# 200W_4FET_Load_v10.net
KiCad netlist of a schematic drawn in EAGLE
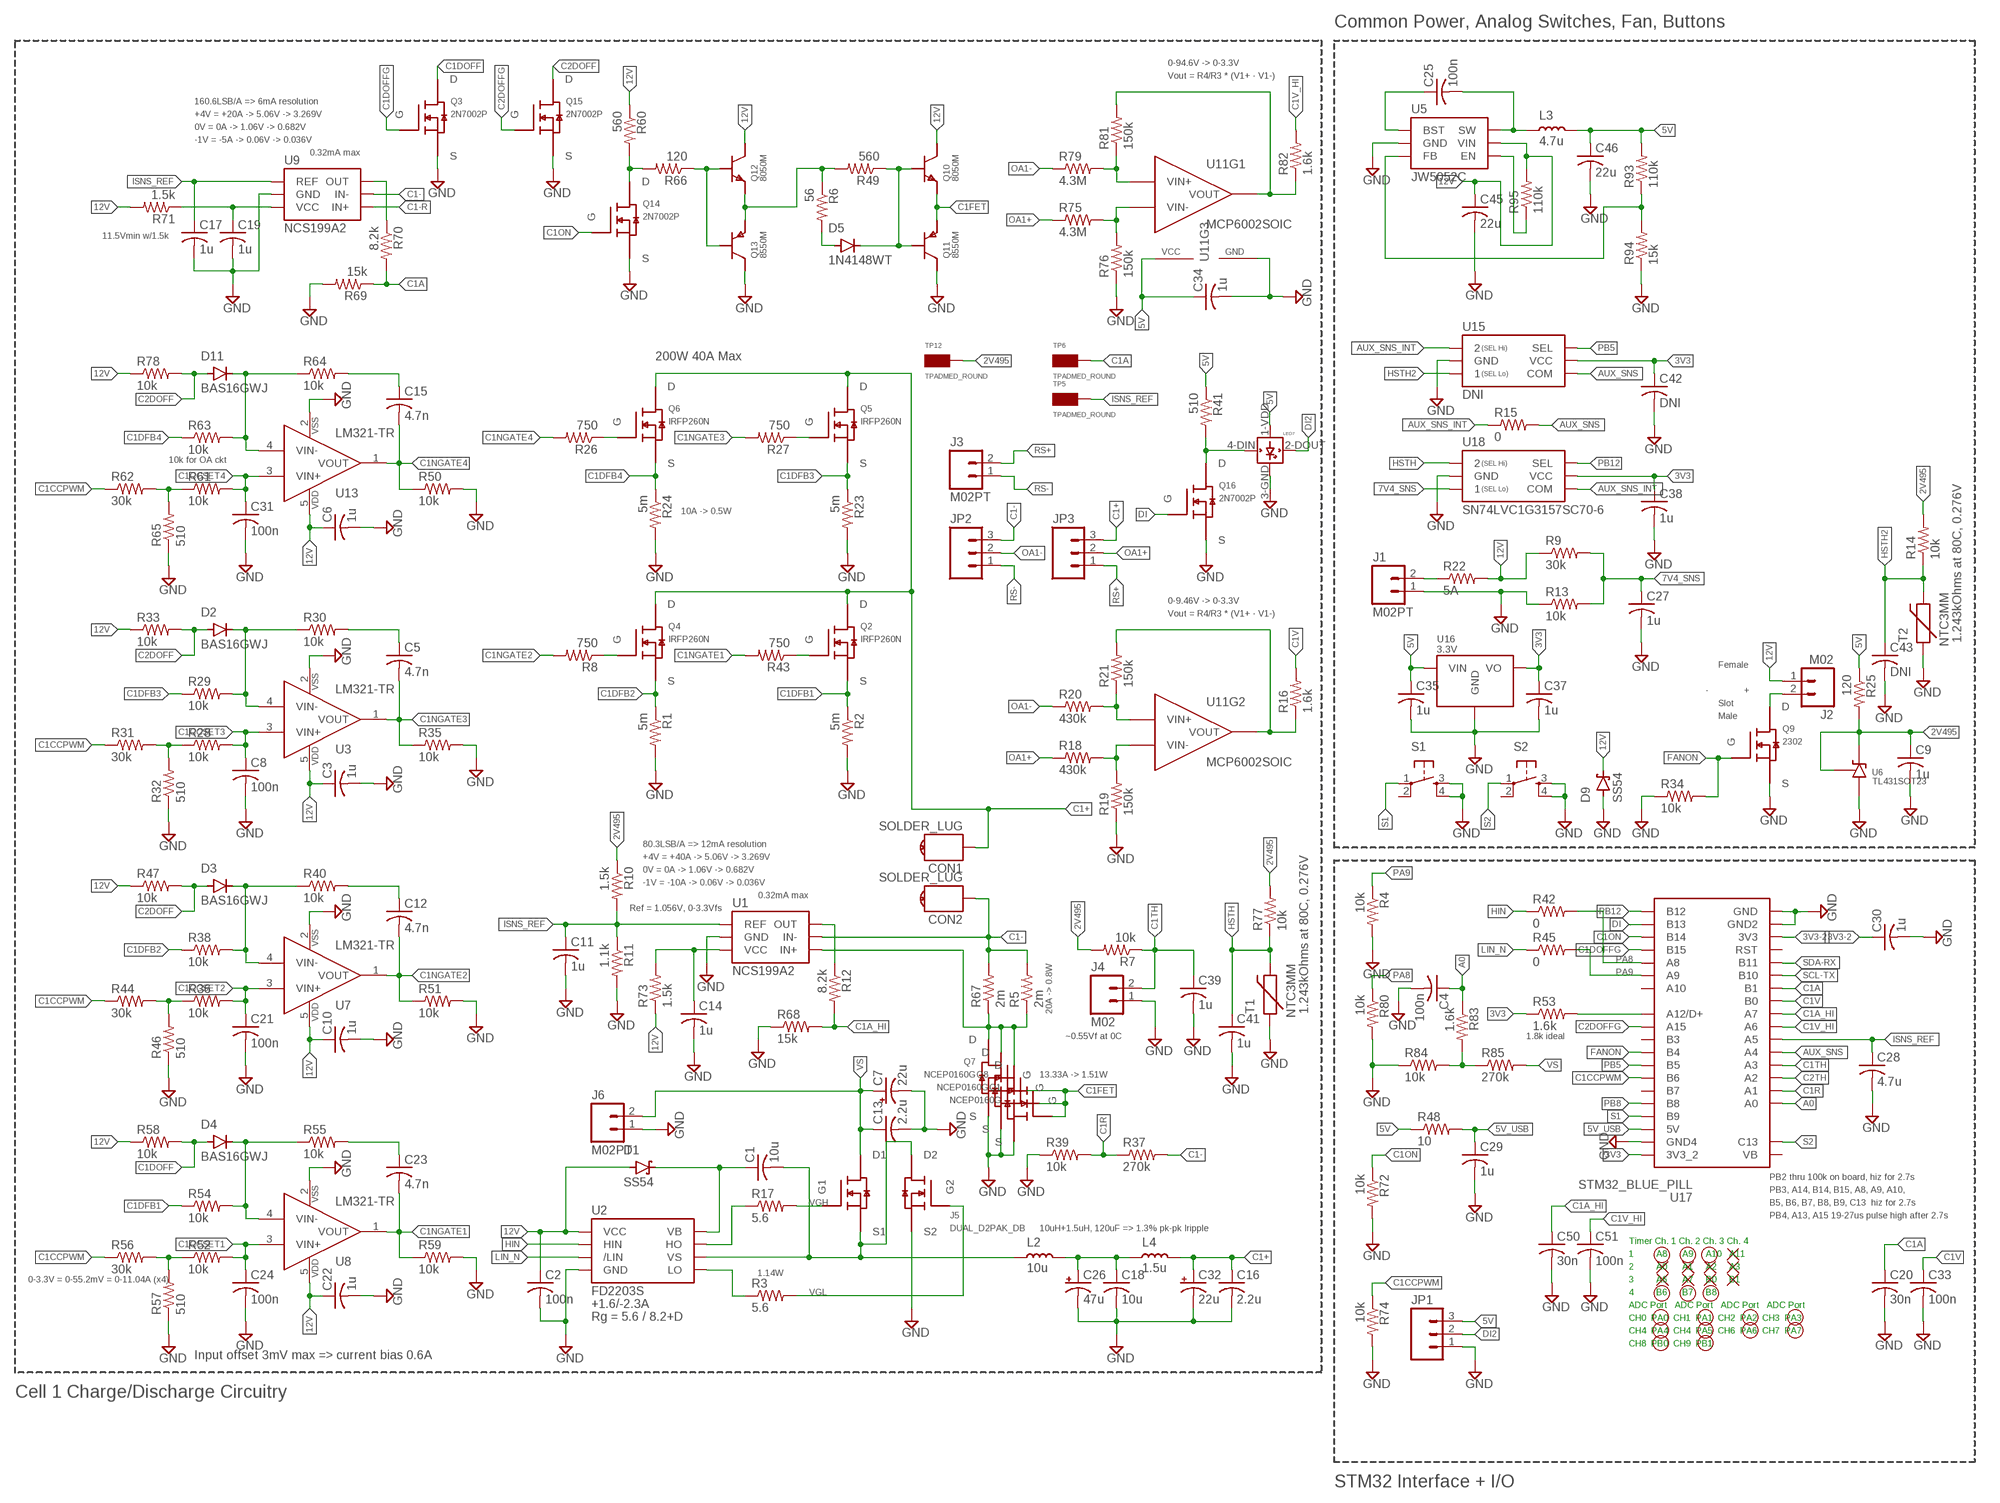
[diagram p0: schematic, sheet 1]

(export (version "E")
  (design (tool "Eeschema 10.0.6"))
  (components
    (comp (ref "C1")
      (value "10u")
      (footprint "eagle-import:C0603")
      (libsource (lib "eagle-import") (part "C-USC0603"))
    )
    (comp (ref "C2")
      (value "100n")
      (footprint "eagle-import:C0603")
      (libsource (lib "eagle-import") (part "C-USC0603"))
    )
    (comp (ref "C3")
      (value "1u")
      (footprint "eagle-import:C0402")
      (libsource (lib "eagle-import") (part "C-USC0402"))
    )
    (comp (ref "C4")
      (value "100n")
      (footprint "eagle-import:C0402")
      (libsource (lib "eagle-import") (part "C-USC0402"))
    )
    (comp (ref "C5")
      (value "4.7n")
      (footprint "eagle-import:C0402")
      (libsource (lib "eagle-import") (part "C-USC0402"))
    )
    (comp (ref "C6")
      (value "1u")
      (footprint "eagle-import:C0402")
      (libsource (lib "eagle-import") (part "C-USC0402"))
    )
    (comp (ref "C7")
      (value "22u")
      (footprint "eagle-import:E2,5-6E")
      (libsource (lib "eagle-import") (part "CPOL-USE2,5-6E"))
    )
    (comp (ref "C8")
      (value "100n")
      (footprint "eagle-import:C0402")
      (libsource (lib "eagle-import") (part "C-USC0402"))
    )
    (comp (ref "C9")
      (value "1u")
      (footprint "eagle-import:C0402")
      (libsource (lib "eagle-import") (part "C-USC0402"))
    )
    (comp (ref "C10")
      (value "1u")
      (footprint "eagle-import:C0402")
      (libsource (lib "eagle-import") (part "C-USC0402"))
    )
    (comp (ref "C11")
      (value "1u")
      (footprint "eagle-import:C0402")
      (libsource (lib "eagle-import") (part "C-USC0402"))
    )
    (comp (ref "C12")
      (value "4.7n")
      (footprint "eagle-import:C0402")
      (libsource (lib "eagle-import") (part "C-USC0402"))
    )
    (comp (ref "C13")
      (value "2.2u")
      (footprint "eagle-import:C1210")
      (libsource (lib "eagle-import") (part "C-USC1210"))
    )
    (comp (ref "C14")
      (value "1u")
      (footprint "eagle-import:C0402")
      (libsource (lib "eagle-import") (part "C-USC0402"))
    )
    (comp (ref "C15")
      (value "4.7n")
      (footprint "eagle-import:C0402")
      (libsource (lib "eagle-import") (part "C-USC0402"))
    )
    (comp (ref "C16")
      (value "2.2u")
      (footprint "eagle-import:C1210")
      (libsource (lib "eagle-import") (part "C-USC1210"))
    )
    (comp (ref "C17")
      (value "1u")
      (footprint "eagle-import:C0402")
      (libsource (lib "eagle-import") (part "C-USC0402"))
    )
    (comp (ref "C18")
      (value "10u")
      (footprint "eagle-import:C2220K")
      (libsource (lib "eagle-import") (part "C-USC2220K"))
    )
    (comp (ref "C19")
      (value "1u")
      (footprint "eagle-import:C0402")
      (libsource (lib "eagle-import") (part "C-USC0402"))
    )
    (comp (ref "C20")
      (value "30n")
      (footprint "eagle-import:C0402")
      (libsource (lib "eagle-import") (part "C-USC0402"))
    )
    (comp (ref "C21")
      (value "100n")
      (footprint "eagle-import:C0402")
      (libsource (lib "eagle-import") (part "C-USC0402"))
    )
    (comp (ref "C22")
      (value "1u")
      (footprint "eagle-import:C0402")
      (libsource (lib "eagle-import") (part "C-USC0402"))
    )
    (comp (ref "C23")
      (value "4.7n")
      (footprint "eagle-import:C0402")
      (libsource (lib "eagle-import") (part "C-USC0402"))
    )
    (comp (ref "C24")
      (value "100n")
      (footprint "eagle-import:C0402")
      (libsource (lib "eagle-import") (part "C-USC0402"))
    )
    (comp (ref "C25")
      (value "100n")
      (footprint "eagle-import:C0402")
      (libsource (lib "eagle-import") (part "C-USC0402"))
    )
    (comp (ref "C26")
      (value "47u")
      (footprint "eagle-import:E3,5-8")
      (libsource (lib "eagle-import") (part "CPOL-USE3.5-8"))
    )
    (comp (ref "C27")
      (value "1u")
      (footprint "eagle-import:C0402")
      (libsource (lib "eagle-import") (part "C-USC0402"))
    )
    (comp (ref "C28")
      (value "4.7u")
      (footprint "eagle-import:C0402")
      (libsource (lib "eagle-import") (part "C-USC0402"))
    )
    (comp (ref "C29")
      (value "1u")
      (footprint "eagle-import:C0402")
      (libsource (lib "eagle-import") (part "C-USC0402"))
    )
    (comp (ref "C30")
      (value "1u")
      (footprint "eagle-import:C0402")
      (libsource (lib "eagle-import") (part "C-USC0402"))
    )
    (comp (ref "C31")
      (value "100n")
      (footprint "eagle-import:C0402")
      (libsource (lib "eagle-import") (part "C-USC0402"))
    )
    (comp (ref "C32")
      (value "22u")
      (footprint "eagle-import:E2,5-6E")
      (libsource (lib "eagle-import") (part "CPOL-USE2,5-6E"))
    )
    (comp (ref "C33")
      (value "100n")
      (footprint "eagle-import:C0402")
      (libsource (lib "eagle-import") (part "C-USC0402"))
    )
    (comp (ref "C34")
      (value "1u")
      (footprint "eagle-import:C0402")
      (libsource (lib "eagle-import") (part "C-USC0402"))
    )
    (comp (ref "C35")
      (value "1u")
      (footprint "eagle-import:C0402")
      (libsource (lib "eagle-import") (part "C-USC0402"))
    )
    (comp (ref "C37")
      (value "1u")
      (footprint "eagle-import:C0402")
      (libsource (lib "eagle-import") (part "C-USC0402"))
    )
    (comp (ref "C38")
      (value "1u")
      (footprint "eagle-import:C0402")
      (libsource (lib "eagle-import") (part "C-USC0402"))
    )
    (comp (ref "C39")
      (value "1u")
      (footprint "eagle-import:C0402")
      (libsource (lib "eagle-import") (part "C-USC0402"))
    )
    (comp (ref "C41")
      (value "1u")
      (footprint "eagle-import:C0402")
      (libsource (lib "eagle-import") (part "C-USC0402"))
    )
    (comp (ref "C42")
      (value "DNI")
      (footprint "eagle-import:C0402")
      (libsource (lib "eagle-import") (part "C-USC0402"))
    )
    (comp (ref "C43")
      (value "DNI")
      (footprint "eagle-import:C0402")
      (libsource (lib "eagle-import") (part "C-USC0402"))
    )
    (comp (ref "C45")
      (value "22u")
      (footprint "eagle-import:C0805")
      (libsource (lib "eagle-import") (part "C-USC0805"))
    )
    (comp (ref "C46")
      (value "22u")
      (footprint "eagle-import:C0603")
      (libsource (lib "eagle-import") (part "C-USC0603"))
    )
    (comp (ref "C50")
      (value "30n")
      (footprint "eagle-import:C0402")
      (libsource (lib "eagle-import") (part "C-USC0402"))
    )
    (comp (ref "C51")
      (value "100n")
      (footprint "eagle-import:C0402")
      (libsource (lib "eagle-import") (part "C-USC0402"))
    )
    (comp (ref "CON1")
      (value "SOLDER_LUG")
      (footprint "eagle-import:M4_RA_SOLDTERM")
      (libsource (lib "eagle-import") (part "SOLDER_LUG"))
    )
    (comp (ref "CON2")
      (value "SOLDER_LUG")
      (footprint "eagle-import:M4_RA_SOLDTERM")
      (libsource (lib "eagle-import") (part "SOLDER_LUG"))
    )
    (comp (ref "D1")
      (value "SS54")
      (footprint "eagle-import:SMA")
      (libsource (lib "eagle-import") (part "SS54"))
    )
    (comp (ref "D2")
      (value "BAS16GWJ")
      (footprint "eagle-import:SOD323")
      (libsource (lib "eagle-import") (part "BAT60A"))
    )
    (comp (ref "D3")
      (value "BAS16GWJ")
      (footprint "eagle-import:SOD323")
      (libsource (lib "eagle-import") (part "BAT60A"))
    )
    (comp (ref "D4")
      (value "BAS16GWJ")
      (footprint "eagle-import:SOD323")
      (libsource (lib "eagle-import") (part "BAT60A"))
    )
    (comp (ref "D5")
      (value "1N4148WT")
      (footprint "eagle-import:SOD523")
      (libsource (lib "eagle-import") (part "1N4148WT"))
    )
    (comp (ref "D9")
      (value "SS54")
      (footprint "eagle-import:SMA")
      (libsource (lib "eagle-import") (part "SS54"))
    )
    (comp (ref "D11")
      (value "BAS16GWJ")
      (footprint "eagle-import:SOD323")
      (libsource (lib "eagle-import") (part "BAT60A"))
    )
    (comp (ref "J1")
      (value "M02PT")
      (footprint "eagle-import:PHOENIXCONTACT1935161")
      (libsource (lib "eagle-import") (part "M02PT"))
    )
    (comp (ref "J2")
      (value "M02")
      (footprint "eagle-import:B2B-XH-A")
      (libsource (lib "eagle-import") (part "M02"))
    )
    (comp (ref "J3")
      (value "M02PT")
      (footprint "eagle-import:PHOENIXCONTACT1935161")
      (libsource (lib "eagle-import") (part "M02PT"))
    )
    (comp (ref "J4")
      (value "M02")
      (footprint "eagle-import:B2B-XH-A")
      (libsource (lib "eagle-import") (part "M02"))
    )
    (comp (ref "J5")
      (value "DUAL_D2PAK_DB")
      (footprint "eagle-import:DUAL_D2PAK_DB")
      (libsource (lib "eagle-import") (part "DUAL_D2PAK_DB"))
    )
    (comp (ref "J6")
      (value "M02PT")
      (footprint "eagle-import:PHOENIXCONTACT1935161")
      (libsource (lib "eagle-import") (part "M02PT"))
    )
    (comp (ref "JP1")
      (value "M03PTH")
      (footprint "eagle-import:1X03")
      (libsource (lib "eagle-import") (part "M03PTH"))
    )
    (comp (ref "JP2")
      (value "M03PTH")
      (footprint "eagle-import:1X03")
      (libsource (lib "eagle-import") (part "M03PTH"))
    )
    (comp (ref "JP3")
      (value "M03PTH")
      (footprint "eagle-import:1X03")
      (libsource (lib "eagle-import") (part "M03PTH"))
    )
    (comp (ref "L2")
      (value "10u")
      (footprint "eagle-import:INDUCTOR_13.8X12.7")
      (libsource (lib "eagle-import") (part "INDUCTOR13P8"))
    )
    (comp (ref "L3")
      (value "4.7u")
      (footprint "eagle-import:0805")
      (libsource (lib "eagle-import") (part "INDUCTOR0805"))
    )
    (comp (ref "L4")
      (value "1.5u")
      (footprint "eagle-import:INDUCTOR_7.4X6.6MM")
      (libsource (lib "eagle-import") (part "INDUCTOR"))
    )
    (comp (ref "LED7")
      (value "WS2812B")
      (footprint "eagle-import:WS2812B")
      (libsource (lib "eagle-import") (part "WS2812B"))
    )
    (comp (ref "Q1")
      (value "NCEP0160G")
      (footprint "eagle-import:DFN5X6-8L")
      (libsource (lib "eagle-import") (part "NCEP0160G"))
    )
    (comp (ref "Q2")
      (value "IRFP260N")
      (footprint "eagle-import:TO-247")
      (libsource (lib "eagle-import") (part "IRFP260N"))
    )
    (comp (ref "Q3")
      (value "2N7002P")
      (footprint "eagle-import:SOT23")
      (libsource (lib "eagle-import") (part "2N7002P"))
    )
    (comp (ref "Q4")
      (value "IRFP260N")
      (footprint "eagle-import:TO-247")
      (libsource (lib "eagle-import") (part "IRFP260N"))
    )
    (comp (ref "Q5")
      (value "IRFP260N")
      (footprint "eagle-import:TO-247")
      (libsource (lib "eagle-import") (part "IRFP260N"))
    )
    (comp (ref "Q6")
      (value "IRFP260N")
      (footprint "eagle-import:TO-247")
      (libsource (lib "eagle-import") (part "IRFP260N"))
    )
    (comp (ref "Q7")
      (value "NCEP0160G")
      (footprint "eagle-import:DFN5X6-8L")
      (libsource (lib "eagle-import") (part "NCEP0160G"))
    )
    (comp (ref "Q8")
      (value "NCEP0160G")
      (footprint "eagle-import:DFN5X6-8L")
      (libsource (lib "eagle-import") (part "NCEP0160G"))
    )
    (comp (ref "Q9")
      (value "2302")
      (footprint "eagle-import:SOT23")
      (libsource (lib "eagle-import") (part "2N7002P"))
    )
    (comp (ref "Q10")
      (value "8050M")
      (footprint "eagle-import:SOT23")
      (libsource (lib "eagle-import") (part "8050M"))
    )
    (comp (ref "Q11")
      (value "8550M")
      (footprint "eagle-import:SOT23")
      (libsource (lib "eagle-import") (part "8550M"))
    )
    (comp (ref "Q12")
      (value "8050M")
      (footprint "eagle-import:SOT23")
      (libsource (lib "eagle-import") (part "8050M"))
    )
    (comp (ref "Q13")
      (value "8550M")
      (footprint "eagle-import:SOT23")
      (libsource (lib "eagle-import") (part "8550M"))
    )
    (comp (ref "Q14")
      (value "2N7002P")
      (footprint "eagle-import:SOT23")
      (libsource (lib "eagle-import") (part "2N7002P"))
    )
    (comp (ref "Q15")
      (value "2N7002P")
      (footprint "eagle-import:SOT23")
      (libsource (lib "eagle-import") (part "2N7002P"))
    )
    (comp (ref "Q16")
      (value "2N7002P")
      (footprint "eagle-import:SOT23")
      (libsource (lib "eagle-import") (part "2N7002P"))
    )
    (comp (ref "R1")
      (value "5m")
      (footprint "eagle-import:R1206")
      (libsource (lib "eagle-import") (part "R-US_R1206"))
    )
    (comp (ref "R2")
      (value "5m")
      (footprint "eagle-import:R1206")
      (libsource (lib "eagle-import") (part "R-US_R1206"))
    )
    (comp (ref "R3")
      (value "5.6")
      (footprint "eagle-import:R2512")
      (libsource (lib "eagle-import") (part "R-US_R2512"))
    )
    (comp (ref "R4")
      (value "10k")
      (footprint "eagle-import:R0402")
      (libsource (lib "eagle-import") (part "R-US_R0402"))
    )
    (comp (ref "R5")
      (value "2m")
      (footprint "eagle-import:R2512")
      (libsource (lib "eagle-import") (part "R-US_R2512"))
    )
    (comp (ref "R6")
      (value "56")
      (footprint "eagle-import:R0402")
      (libsource (lib "eagle-import") (part "R-US_R0402"))
    )
    (comp (ref "R7")
      (value "10k")
      (footprint "eagle-import:R0402")
      (libsource (lib "eagle-import") (part "R-US_R0402"))
    )
    (comp (ref "R8")
      (value "750")
      (footprint "eagle-import:R0402")
      (libsource (lib "eagle-import") (part "R-US_R0402"))
    )
    (comp (ref "R9")
      (value "30k")
      (footprint "eagle-import:R0402")
      (libsource (lib "eagle-import") (part "R-US_R0402"))
    )
    (comp (ref "R10")
      (value "1.5k")
      (footprint "eagle-import:R0402")
      (libsource (lib "eagle-import") (part "R-US_R0402"))
    )
    (comp (ref "R11")
      (value "1.1k")
      (footprint "eagle-import:R0402")
      (libsource (lib "eagle-import") (part "R-US_R0402"))
    )
    (comp (ref "R12")
      (value "8.2k")
      (footprint "eagle-import:R0402")
      (libsource (lib "eagle-import") (part "R-US_R0402"))
    )
    (comp (ref "R13")
      (value "10k")
      (footprint "eagle-import:R0402")
      (libsource (lib "eagle-import") (part "R-US_R0402"))
    )
    (comp (ref "R14")
      (value "10k")
      (footprint "eagle-import:R0402")
      (libsource (lib "eagle-import") (part "R-US_R0402"))
    )
    (comp (ref "R15")
      (value "0")
      (footprint "eagle-import:R0402")
      (libsource (lib "eagle-import") (part "R-US_R0402"))
    )
    (comp (ref "R16")
      (value "1.6k")
      (footprint "eagle-import:R0402")
      (libsource (lib "eagle-import") (part "R-US_R0402"))
    )
    (comp (ref "R17")
      (value "5.6")
      (footprint "eagle-import:R2512")
      (libsource (lib "eagle-import") (part "R-US_R2512"))
    )
    (comp (ref "R18")
      (value "430k")
      (footprint "eagle-import:R0402")
      (libsource (lib "eagle-import") (part "R-US_R0402"))
    )
    (comp (ref "R19")
      (value "150k")
      (footprint "eagle-import:R0402")
      (libsource (lib "eagle-import") (part "R-US_R0402"))
    )
    (comp (ref "R20")
      (value "430k")
      (footprint "eagle-import:R0402")
      (libsource (lib "eagle-import") (part "R-US_R0402"))
    )
    (comp (ref "R21")
      (value "150k")
      (footprint "eagle-import:R0402")
      (libsource (lib "eagle-import") (part "R-US_R0402"))
    )
    (comp (ref "R22")
      (value "5A")
      (footprint "eagle-import:R1206")
      (libsource (lib "eagle-import") (part "R-US_R1206"))
    )
    (comp (ref "R23")
      (value "5m")
      (footprint "eagle-import:R1206")
      (libsource (lib "eagle-import") (part "R-US_R1206"))
    )
    (comp (ref "R24")
      (value "5m")
      (footprint "eagle-import:R1206")
      (libsource (lib "eagle-import") (part "R-US_R1206"))
    )
    (comp (ref "R25")
      (value "120")
      (footprint "eagle-import:R0402")
      (libsource (lib "eagle-import") (part "R-US_R0402"))
    )
    (comp (ref "R26")
      (value "750")
      (footprint "eagle-import:R0402")
      (libsource (lib "eagle-import") (part "R-US_R0402"))
    )
    (comp (ref "R27")
      (value "750")
      (footprint "eagle-import:R0402")
      (libsource (lib "eagle-import") (part "R-US_R0402"))
    )
    (comp (ref "R28")
      (value "10k")
      (footprint "eagle-import:R0402")
      (libsource (lib "eagle-import") (part "R-US_R0402"))
    )
    (comp (ref "R29")
      (value "10k")
      (footprint "eagle-import:R0402")
      (libsource (lib "eagle-import") (part "R-US_R0402"))
    )
    (comp (ref "R30")
      (value "10k")
      (footprint "eagle-import:R0402")
      (libsource (lib "eagle-import") (part "R-US_R0402"))
    )
    (comp (ref "R31")
      (value "30k")
      (footprint "eagle-import:R0402")
      (libsource (lib "eagle-import") (part "R-US_R0402"))
    )
    (comp (ref "R32")
      (value "510")
      (footprint "eagle-import:R0402")
      (libsource (lib "eagle-import") (part "R-US_R0402"))
    )
    (comp (ref "R33")
      (value "10k")
      (footprint "eagle-import:R0402")
      (libsource (lib "eagle-import") (part "R-US_R0402"))
    )
    (comp (ref "R34")
      (value "10k")
      (footprint "eagle-import:R0402")
      (libsource (lib "eagle-import") (part "R-US_R0402"))
    )
    (comp (ref "R35")
      (value "10k")
      (footprint "eagle-import:R0402")
      (libsource (lib "eagle-import") (part "R-US_R0402"))
    )
    (comp (ref "R36")
      (value "10k")
      (footprint "eagle-import:R0402")
      (libsource (lib "eagle-import") (part "R-US_R0402"))
    )
    (comp (ref "R37")
      (value "270k")
      (footprint "eagle-import:R0402")
      (libsource (lib "eagle-import") (part "R-US_R0402"))
    )
    (comp (ref "R38")
      (value "10k")
      (footprint "eagle-import:R0402")
      (libsource (lib "eagle-import") (part "R-US_R0402"))
    )
    (comp (ref "R39")
      (value "10k")
      (footprint "eagle-import:R0402")
      (libsource (lib "eagle-import") (part "R-US_R0402"))
    )
    (comp (ref "R40")
      (value "10k")
      (footprint "eagle-import:R0402")
      (libsource (lib "eagle-import") (part "R-US_R0402"))
    )
    (comp (ref "R41")
      (value "510")
      (footprint "eagle-import:R0402")
      (libsource (lib "eagle-import") (part "R-US_R0402"))
    )
    (comp (ref "R42")
      (value "0")
      (footprint "eagle-import:R0402")
      (libsource (lib "eagle-import") (part "R-US_R0402"))
    )
    (comp (ref "R43")
      (value "750")
      (footprint "eagle-import:R0402")
      (libsource (lib "eagle-import") (part "R-US_R0402"))
    )
    (comp (ref "R44")
      (value "30k")
      (footprint "eagle-import:R0402")
      (libsource (lib "eagle-import") (part "R-US_R0402"))
    )
    (comp (ref "R45")
      (value "0")
      (footprint "eagle-import:R0402")
      (libsource (lib "eagle-import") (part "R-US_R0402"))
    )
    (comp (ref "R46")
      (value "510")
      (footprint "eagle-import:R0402")
      (libsource (lib "eagle-import") (part "R-US_R0402"))
    )
    (comp (ref "R47")
      (value "10k")
      (footprint "eagle-import:R0402")
      (libsource (lib "eagle-import") (part "R-US_R0402"))
    )
    (comp (ref "R48")
      (value "10")
      (footprint "eagle-import:R0402")
      (libsource (lib "eagle-import") (part "R-US_R0402"))
    )
    (comp (ref "R49")
      (value "560")
      (footprint "eagle-import:R0402")
      (libsource (lib "eagle-import") (part "R-US_R0402"))
    )
    (comp (ref "R50")
      (value "10k")
      (footprint "eagle-import:R0402")
      (libsource (lib "eagle-import") (part "R-US_R0402"))
    )
    (comp (ref "R51")
      (value "10k")
      (footprint "eagle-import:R0402")
      (libsource (lib "eagle-import") (part "R-US_R0402"))
    )
    (comp (ref "R52")
      (value "10k")
      (footprint "eagle-import:R0402")
      (libsource (lib "eagle-import") (part "R-US_R0402"))
    )
    (comp (ref "R53")
      (value "1.6k")
      (footprint "eagle-import:R0402")
      (libsource (lib "eagle-import") (part "R-US_R0402"))
    )
    (comp (ref "R54")
      (value "10k")
      (footprint "eagle-import:R0402")
      (libsource (lib "eagle-import") (part "R-US_R0402"))
    )
    (comp (ref "R55")
      (value "10k")
      (footprint "eagle-import:R0402")
      (libsource (lib "eagle-import") (part "R-US_R0402"))
    )
    (comp (ref "R56")
      (value "30k")
      (footprint "eagle-import:R0402")
      (libsource (lib "eagle-import") (part "R-US_R0402"))
    )
    (comp (ref "R57")
      (value "510")
      (footprint "eagle-import:R0402")
      (libsource (lib "eagle-import") (part "R-US_R0402"))
    )
    (comp (ref "R58")
      (value "10k")
      (footprint "eagle-import:R0402")
      (libsource (lib "eagle-import") (part "R-US_R0402"))
    )
    (comp (ref "R59")
      (value "10k")
      (footprint "eagle-import:R0402")
      (libsource (lib "eagle-import") (part "R-US_R0402"))
    )
    (comp (ref "R60")
      (value "560")
      (footprint "eagle-import:R0402")
      (libsource (lib "eagle-import") (part "R-US_R0402"))
    )
    (comp (ref "R61")
      (value "10k")
      (footprint "eagle-import:R0402")
      (libsource (lib "eagle-import") (part "R-US_R0402"))
    )
    (comp (ref "R62")
      (value "30k")
      (footprint "eagle-import:R0402")
      (libsource (lib "eagle-import") (part "R-US_R0402"))
    )
    (comp (ref "R63")
      (value "10k")
      (footprint "eagle-import:R0402")
      (libsource (lib "eagle-import") (part "R-US_R0402"))
    )
    (comp (ref "R64")
      (value "10k")
      (footprint "eagle-import:R0402")
      (libsource (lib "eagle-import") (part "R-US_R0402"))
    )
    (comp (ref "R65")
      (value "510")
      (footprint "eagle-import:R0402")
      (libsource (lib "eagle-import") (part "R-US_R0402"))
    )
    (comp (ref "R66")
      (value "120")
      (footprint "eagle-import:R0402")
      (libsource (lib "eagle-import") (part "R-US_R0402"))
    )
    (comp (ref "R67")
      (value "2m")
      (footprint "eagle-import:R2512")
      (libsource (lib "eagle-import") (part "R-US_R2512"))
    )
    (comp (ref "R68")
      (value "15k")
      (footprint "eagle-import:R0402")
      (libsource (lib "eagle-import") (part "R-US_R0402"))
    )
    (comp (ref "R69")
      (value "15k")
      (footprint "eagle-import:R0402")
      (libsource (lib "eagle-import") (part "R-US_R0402"))
    )
    (comp (ref "R70")
      (value "8.2k")
      (footprint "eagle-import:R0402")
      (libsource (lib "eagle-import") (part "R-US_R0402"))
    )
    (comp (ref "R71")
      (value "1.5k")
      (footprint "eagle-import:R0402")
      (libsource (lib "eagle-import") (part "R-US_R0402"))
    )
    (comp (ref "R72")
      (value "10k")
      (footprint "eagle-import:R0402")
      (libsource (lib "eagle-import") (part "R-US_R0402"))
    )
    (comp (ref "R73")
      (value "1.5k")
      (footprint "eagle-import:R0402")
      (libsource (lib "eagle-import") (part "R-US_R0402"))
    )
    (comp (ref "R74")
      (value "10k")
      (footprint "eagle-import:R0402")
      (libsource (lib "eagle-import") (part "R-US_R0402"))
    )
    (comp (ref "R75")
      (value "4.3M")
      (footprint "eagle-import:R0402")
      (libsource (lib "eagle-import") (part "R-US_R0402"))
    )
    (comp (ref "R76")
      (value "150k")
      (footprint "eagle-import:R0402")
      (libsource (lib "eagle-import") (part "R-US_R0402"))
    )
    (comp (ref "R77")
      (value "10k")
      (footprint "eagle-import:R0402")
      (libsource (lib "eagle-import") (part "R-US_R0402"))
    )
    (comp (ref "R78")
      (value "10k")
      (footprint "eagle-import:R0402")
      (libsource (lib "eagle-import") (part "R-US_R0402"))
    )
    (comp (ref "R79")
      (value "4.3M")
      (footprint "eagle-import:R0402")
      (libsource (lib "eagle-import") (part "R-US_R0402"))
    )
    (comp (ref "R80")
      (value "10k")
      (footprint "eagle-import:R0402")
      (libsource (lib "eagle-import") (part "R-US_R0402"))
    )
    (comp (ref "R81")
      (value "150k")
      (footprint "eagle-import:R0402")
      (libsource (lib "eagle-import") (part "R-US_R0402"))
    )
    (comp (ref "R82")
      (value "1.6k")
      (footprint "eagle-import:R0402")
      (libsource (lib "eagle-import") (part "R-US_R0402"))
    )
    (comp (ref "R83")
      (value "1.6k")
      (footprint "eagle-import:R0402")
      (libsource (lib "eagle-import") (part "R-US_R0402"))
    )
    (comp (ref "R84")
      (value "10k")
      (footprint "eagle-import:R0402")
      (libsource (lib "eagle-import") (part "R-US_R0402"))
    )
    (comp (ref "R85")
      (value "270k")
      (footprint "eagle-import:R0402")
      (libsource (lib "eagle-import") (part "R-US_R0402"))
    )
    (comp (ref "R93")
      (value "110k")
      (footprint "eagle-import:R0402")
      (libsource (lib "eagle-import") (part "R-US_R0402"))
    )
    (comp (ref "R94")
      (value "15k")
      (footprint "eagle-import:R0402")
      (libsource (lib "eagle-import") (part "R-US_R0402"))
    )
    (comp (ref "R95")
      (value "110k")
      (footprint "eagle-import:R0402")
      (libsource (lib "eagle-import") (part "R-US_R0402"))
    )
    (comp (ref "S1")
      (value "TAC_SWITCHSMD")
      (footprint "eagle-import:TACTILE_SWITCH_SMD")
      (libsource (lib "eagle-import") (part "TAC_SWITCHSMD"))
    )
    (comp (ref "S2")
      (value "TAC_SWITCHSMD")
      (footprint "eagle-import:TACTILE_SWITCH_SMD")
      (libsource (lib "eagle-import") (part "TAC_SWITCHSMD"))
    )
    (comp (ref "T1")
      (value "NTC3MM")
      (footprint "eagle-import:THERMISTOR_3MMX3MM")
      (libsource (lib "eagle-import") (part "PTCNTC3MM"))
    )
    (comp (ref "T2")
      (value "NTC3MM")
      (footprint "eagle-import:THERMISTOR_3MMX3MM")
      (libsource (lib "eagle-import") (part "PTCNTC3MM"))
    )
    (comp (ref "TP5")
      (value "TPADMED_ROUND")
      (footprint "eagle-import:TPAD_MED_ROUND")
      (libsource (lib "eagle-import") (part "TPADMED_ROUND"))
    )
    (comp (ref "TP6")
      (value "TPADMED_ROUND")
      (footprint "eagle-import:TPAD_MED_ROUND")
      (libsource (lib "eagle-import") (part "TPADMED_ROUND"))
    )
    (comp (ref "TP12")
      (value "TPADMED_ROUND")
      (footprint "eagle-import:TPAD_MED_ROUND")
      (libsource (lib "eagle-import") (part "TPADMED_ROUND"))
    )
    (comp (ref "U1")
      (value "NCS199A2")
      (footprint "eagle-import:SOT-363")
      (libsource (lib "eagle-import") (part "INA214"))
    )
    (comp (ref "U2")
      (value "FD2203S")
      (footprint "eagle-import:8-SOIC")
      (libsource (lib "eagle-import") (part "EG2131"))
    )
    (comp (ref "U3")
      (value "LM321-TR")
      (footprint "eagle-import:SOT23-5")
      (libsource (lib "eagle-import") (part "NCS325"))
    )
    (comp (ref "U5")
      (value "JW5052C")
      (footprint "eagle-import:SOT23-6")
      (libsource (lib "eagle-import") (part "JW5052C"))
    )
    (comp (ref "U6")
      (value "TL431SOT23")
      (footprint "eagle-import:SOT23")
      (libsource (lib "eagle-import") (part "TL431SOT23"))
    )
    (comp (ref "U7")
      (value "LM321-TR")
      (footprint "eagle-import:SOT23-5")
      (libsource (lib "eagle-import") (part "NCS325"))
    )
    (comp (ref "U8")
      (value "LM321-TR")
      (footprint "eagle-import:SOT23-5")
      (libsource (lib "eagle-import") (part "NCS325"))
    )
    (comp (ref "U9")
      (value "NCS199A2")
      (footprint "eagle-import:SOT-363")
      (libsource (lib "eagle-import") (part "INA214"))
    )
    (comp (ref "U11")
      (value "MCP6002SOIC")
      (footprint "eagle-import:8-SOIC")
      (libsource (lib "eagle-import") (part "MCP6002SOIC"))
    )
    (comp (ref "U13")
      (value "LM321-TR")
      (footprint "eagle-import:SOT23-5")
      (libsource (lib "eagle-import") (part "NCS325"))
    )
    (comp (ref "U15")
      (value "DNI")
      (footprint "eagle-import:SC70-6")
      (libsource (lib "eagle-import") (part "SN74LVC1G3157SC70-6"))
    )
    (comp (ref "U16")
      (value "3.3V")
      (footprint "eagle-import:SOT-89")
      (libsource (lib "eagle-import") (part "AP1117UR133-B"))
    )
    (comp (ref "U17")
      (value "STM32_BLUE_PILL")
      (footprint "eagle-import:STM32_BLUE_PILL_USABLE")
      (libsource (lib "eagle-import") (part "STM32_BLUE_PILL"))
    )
    (comp (ref "U18")
      (value "SN74LVC1G3157SC70-6")
      (footprint "eagle-import:SC70-6")
      (libsource (lib "eagle-import") (part "SN74LVC1G3157SC70-6"))
    )
  )
  (nets
    (net (code "1") (name "/VGH") (class "Default")
      (node (ref "J5") (pin "G1") (pinfunction "G1_G1") (pintype "bidirectional"))
      (node (ref "R17") (pin "2") (pinfunction "2_2") (pintype "passive"))
    )
    (net (code "2") (name "/VGL") (class "Default")
      (node (ref "J5") (pin "G2") (pinfunction "G2_G2") (pintype "bidirectional"))
      (node (ref "R3") (pin "2") (pinfunction "2_2") (pintype "passive"))
    )
    (net (code "3") (name "2V495") (class "Default")
      (node (ref "C9") (pin "1") (pinfunction "1_1") (pintype "passive"))
      (node (ref "R10") (pin "1") (pinfunction "1_1") (pintype "passive"))
      (node (ref "R14") (pin "2") (pinfunction "2_2") (pintype "passive"))
      (node (ref "R25") (pin "2") (pinfunction "2_2") (pintype "passive"))
      (node (ref "R7") (pin "2") (pinfunction "2_2") (pintype "passive"))
      (node (ref "R77") (pin "2") (pinfunction "2_2") (pintype "passive"))
      (node (ref "TP12") (pin "1") (pinfunction "1_1") (pintype "bidirectional"))
      (node (ref "U6") (pin "1") (pinfunction "K_1") (pintype "passive"))
      (node (ref "U6") (pin "2") (pinfunction "REF_2") (pintype "passive"))
    )
    (net (code "4") (name "3V3") (class "Default")
      (node (ref "C37") (pin "1") (pinfunction "1_1") (pintype "passive"))
      (node (ref "C38") (pin "1") (pinfunction "1_1") (pintype "passive"))
      (node (ref "C42") (pin "1") (pinfunction "1_1") (pintype "passive"))
      (node (ref "R53") (pin "1") (pinfunction "1_1") (pintype "passive"))
      (node (ref "U15") (pin "5") (pinfunction "VCC_5") (pintype "bidirectional"))
      (node (ref "U16") (pin "1") (pinfunction "VO_1") (pintype "bidirectional"))
      (node (ref "U17") (pin "3V3_2") (pinfunction "3V3_2_3V3_2") (pintype "bidirectional"))
      (node (ref "U18") (pin "5") (pinfunction "VCC_5") (pintype "bidirectional"))
    )
    (net (code "5") (name "3V3-2") (class "Default")
      (node (ref "C30") (pin "1") (pinfunction "1_1") (pintype "passive"))
      (node (ref "U17") (pin "3V3") (pinfunction "3V3_3V3") (pintype "bidirectional"))
    )
    (net (code "6") (name "5V") (class "Default")
      (node (ref "C34") (pin "1") (pinfunction "1_1") (pintype "passive"))
      (node (ref "C35") (pin "1") (pinfunction "1_1") (pintype "passive"))
      (node (ref "C46") (pin "1") (pinfunction "1_1") (pintype "passive"))
      (node (ref "JP1") (pin "3") (pinfunction "3_3") (pintype "passive"))
      (node (ref "L3") (pin "2") (pinfunction "P$2_2") (pintype "passive"))
      (node (ref "LED7") (pin "1-VDD") (pinfunction "VDD_1-VDD") (pintype "bidirectional"))
      (node (ref "R25") (pin "1") (pinfunction "1_1") (pintype "passive"))
      (node (ref "R41") (pin "1") (pinfunction "1_1") (pintype "passive"))
      (node (ref "R48") (pin "1") (pinfunction "1_1") (pintype "passive"))
      (node (ref "R93") (pin "2") (pinfunction "2_2") (pintype "passive"))
      (node (ref "U11") (pin "8") (pinfunction "VCC_8") (pintype "power_in"))
      (node (ref "U16") (pin "3") (pinfunction "VIN_3") (pintype "bidirectional"))
    )
    (net (code "7") (name "5V_USB") (class "Default")
      (node (ref "C29") (pin "1") (pinfunction "1_1") (pintype "passive"))
      (node (ref "R48") (pin "2") (pinfunction "2_2") (pintype "passive"))
      (node (ref "U17") (pin "5V") (pinfunction "5V_5V") (pintype "bidirectional"))
    )
    (net (code "8") (name "7V4_SNS") (class "Default")
      (node (ref "C27") (pin "1") (pinfunction "1_1") (pintype "passive"))
      (node (ref "R13") (pin "2") (pinfunction "2_2") (pintype "passive"))
      (node (ref "R9") (pin "2") (pinfunction "2_2") (pintype "passive"))
      (node (ref "U18") (pin "3") (pinfunction "1_3") (pintype "bidirectional"))
    )
    (net (code "9") (name "12V") (class "Default")
      (node (ref "C10") (pin "1") (pinfunction "1_1") (pintype "passive"))
      (node (ref "C2") (pin "1") (pinfunction "1_1") (pintype "passive"))
      (node (ref "C22") (pin "1") (pinfunction "1_1") (pintype "passive"))
      (node (ref "C3") (pin "1") (pinfunction "1_1") (pintype "passive"))
      (node (ref "C45") (pin "1") (pinfunction "1_1") (pintype "passive"))
      (node (ref "C6") (pin "1") (pinfunction "1_1") (pintype "passive"))
      (node (ref "D1") (pin "A") (pinfunction "ANODE_A") (pintype "passive"))
      (node (ref "D9") (pin "K") (pinfunction "CATHODE_K") (pintype "passive"))
      (node (ref "J2") (pin "1") (pinfunction "1_1") (pintype "passive"))
      (node (ref "Q10") (pin "3") (pinfunction "C_3") (pintype "bidirectional"))
      (node (ref "Q12") (pin "3") (pinfunction "C_3") (pintype "bidirectional"))
      (node (ref "R22") (pin "2") (pinfunction "2_2") (pintype "passive"))
      (node (ref "R33") (pin "1") (pinfunction "1_1") (pintype "passive"))
      (node (ref "R47") (pin "1") (pinfunction "1_1") (pintype "passive"))
      (node (ref "R58") (pin "1") (pinfunction "1_1") (pintype "passive"))
      (node (ref "R60") (pin "1") (pinfunction "1_1") (pintype "passive"))
      (node (ref "R71") (pin "2") (pinfunction "2_2") (pintype "passive"))
      (node (ref "R73") (pin "1") (pinfunction "1_1") (pintype "passive"))
      (node (ref "R78") (pin "1") (pinfunction "1_1") (pintype "passive"))
      (node (ref "R9") (pin "1") (pinfunction "1_1") (pintype "passive"))
      (node (ref "R95") (pin "2") (pinfunction "2_2") (pintype "passive"))
      (node (ref "U13") (pin "5") (pinfunction "VDD_5") (pintype "bidirectional"))
      (node (ref "U2") (pin "1") (pinfunction "VCC_1") (pintype "bidirectional"))
      (node (ref "U3") (pin "5") (pinfunction "VDD_5") (pintype "bidirectional"))
      (node (ref "U5") (pin "5") (pinfunction "VIN_5") (pintype "bidirectional"))
      (node (ref "U7") (pin "5") (pinfunction "VDD_5") (pintype "bidirectional"))
      (node (ref "U8") (pin "5") (pinfunction "VDD_5") (pintype "bidirectional"))
    )
    (net (code "10") (name "A0") (class "Default")
      (node (ref "C4") (pin "1") (pinfunction "1_1") (pintype "passive"))
      (node (ref "R83") (pin "1") (pinfunction "1_1") (pintype "passive"))
      (node (ref "U17") (pin "A0") (pinfunction "A0_A0") (pintype "bidirectional"))
    )
    (net (code "11") (name "AUX_SNS") (class "Default")
      (node (ref "R15") (pin "2") (pinfunction "2_2") (pintype "passive"))
      (node (ref "U15") (pin "4") (pinfunction "COM_4") (pintype "bidirectional"))
      (node (ref "U17") (pin "A4") (pinfunction "A4_A4") (pintype "bidirectional"))
    )
    (net (code "12") (name "AUX_SNS_INT") (class "Default")
      (node (ref "R15") (pin "1") (pinfunction "1_1") (pintype "passive"))
      (node (ref "U15") (pin "1") (pinfunction "2_1") (pintype "bidirectional"))
      (node (ref "U18") (pin "4") (pinfunction "COM_4") (pintype "bidirectional"))
    )
    (net (code "13") (name "C1+") (class "Default")
      (node (ref "C16") (pin "1") (pinfunction "1_1") (pintype "passive"))
      (node (ref "C32") (pin "+") (pinfunction "+_+") (pintype "passive"))
      (node (ref "CON1") (pin "P$1") (pinfunction "P$1_P$1") (pintype "bidirectional"))
      (node (ref "CON1") (pin "P$2") (pinfunction "P$1_P$2") (pintype "bidirectional"))
      (node (ref "CON1") (pin "P$3") (pinfunction "P$1_P$3") (pintype "bidirectional"))
      (node (ref "CON1") (pin "P$4") (pinfunction "P$1_P$4") (pintype "bidirectional"))
      (node (ref "JP3") (pin "3") (pinfunction "3_3") (pintype "passive"))
      (node (ref "L4") (pin "2") (pinfunction "P$2_2") (pintype "passive"))
      (node (ref "Q2") (pin "2") (pinfunction "D_2") (pintype "bidirectional"))
      (node (ref "Q4") (pin "2") (pinfunction "D_2") (pintype "bidirectional"))
      (node (ref "Q5") (pin "2") (pinfunction "D_2") (pintype "bidirectional"))
      (node (ref "Q6") (pin "2") (pinfunction "D_2") (pintype "bidirectional"))
    )
    (net (code "14") (name "C1-") (class "Default")
      (node (ref "CON2") (pin "P$1") (pinfunction "P$1_P$1") (pintype "bidirectional"))
      (node (ref "CON2") (pin "P$2") (pinfunction "P$1_P$2") (pintype "bidirectional"))
      (node (ref "CON2") (pin "P$3") (pinfunction "P$1_P$3") (pintype "bidirectional"))
      (node (ref "CON2") (pin "P$4") (pinfunction "P$1_P$4") (pintype "bidirectional"))
      (node (ref "JP2") (pin "3") (pinfunction "3_3") (pintype "passive"))
      (node (ref "R37") (pin "2") (pinfunction "2_2") (pintype "passive"))
      (node (ref "R5") (pin "2") (pinfunction "2_2") (pintype "passive"))
      (node (ref "R67") (pin "2") (pinfunction "2_2") (pintype "passive"))
      (node (ref "U1") (pin "5") (pinfunction "IN-_5") (pintype "bidirectional"))
      (node (ref "U9") (pin "5") (pinfunction "IN-_5") (pintype "bidirectional"))
    )
    (net (code "15") (name "C1-R") (class "Default")
      (node (ref "Q1") (pin "EP") (pinfunction "D_EP") (pintype "bidirectional"))
      (node (ref "Q1") (pin "EP-TL") (pinfunction "D_EP-TL") (pintype "bidirectional"))
      (node (ref "Q1") (pin "EP-TLL") (pinfunction "D_EP-TLL") (pintype "bidirectional"))
      (node (ref "Q1") (pin "EP-TR") (pinfunction "D_EP-TR") (pintype "bidirectional"))
      (node (ref "Q1") (pin "EP-TRR") (pinfunction "D_EP-TRR") (pintype "bidirectional"))
      (node (ref "Q7") (pin "EP") (pinfunction "D_EP") (pintype "bidirectional"))
      (node (ref "Q7") (pin "EP-TL") (pinfunction "D_EP-TL") (pintype "bidirectional"))
      (node (ref "Q7") (pin "EP-TLL") (pinfunction "D_EP-TLL") (pintype "bidirectional"))
      (node (ref "Q7") (pin "EP-TR") (pinfunction "D_EP-TR") (pintype "bidirectional"))
      (node (ref "Q7") (pin "EP-TRR") (pinfunction "D_EP-TRR") (pintype "bidirectional"))
      (node (ref "Q8") (pin "EP") (pinfunction "D_EP") (pintype "bidirectional"))
      (node (ref "Q8") (pin "EP-TL") (pinfunction "D_EP-TL") (pintype "bidirectional"))
      (node (ref "Q8") (pin "EP-TLL") (pinfunction "D_EP-TLL") (pintype "bidirectional"))
      (node (ref "Q8") (pin "EP-TR") (pinfunction "D_EP-TR") (pintype "bidirectional"))
      (node (ref "Q8") (pin "EP-TRR") (pinfunction "D_EP-TRR") (pintype "bidirectional"))
      (node (ref "R5") (pin "1") (pinfunction "1_1") (pintype "passive"))
      (node (ref "R67") (pin "1") (pinfunction "1_1") (pintype "passive"))
      (node (ref "U1") (pin "4") (pinfunction "IN+_4") (pintype "bidirectional"))
      (node (ref "U9") (pin "4") (pinfunction "IN+_4") (pintype "bidirectional"))
    )
    (net (code "16") (name "C1A") (class "Default")
      (node (ref "C20") (pin "1") (pinfunction "1_1") (pintype "passive"))
      (node (ref "R69") (pin "1") (pinfunction "1_1") (pintype "passive"))
      (node (ref "R70") (pin "2") (pinfunction "2_2") (pintype "passive"))
      (node (ref "TP6") (pin "1") (pinfunction "1_1") (pintype "bidirectional"))
      (node (ref "U17") (pin "B1") (pinfunction "B1_B1") (pintype "bidirectional"))
    )
    (net (code "17") (name "C1A_HI") (class "Default")
      (node (ref "C50") (pin "1") (pinfunction "1_1") (pintype "passive"))
      (node (ref "R12") (pin "2") (pinfunction "2_2") (pintype "passive"))
      (node (ref "R68") (pin "2") (pinfunction "2_2") (pintype "passive"))
      (node (ref "U17") (pin "A7") (pinfunction "A7_A7") (pintype "bidirectional"))
    )
    (net (code "18") (name "C1CCPWM") (class "Default")
      (node (ref "R31") (pin "1") (pinfunction "1_1") (pintype "passive"))
      (node (ref "R44") (pin "1") (pinfunction "1_1") (pintype "passive"))
      (node (ref "R56") (pin "1") (pinfunction "1_1") (pintype "passive"))
      (node (ref "R62") (pin "1") (pinfunction "1_1") (pintype "passive"))
      (node (ref "R74") (pin "1") (pinfunction "1_1") (pintype "passive"))
      (node (ref "U17") (pin "B6") (pinfunction "B6_B6") (pintype "bidirectional"))
    )
    (net (code "19") (name "C1CCSET1") (class "Default")
      (node (ref "C24") (pin "1") (pinfunction "1_1") (pintype "passive"))
      (node (ref "R52") (pin "2") (pinfunction "2_2") (pintype "passive"))
      (node (ref "U8") (pin "3") (pinfunction "VIN+_3") (pintype "bidirectional"))
    )
    (net (code "20") (name "C1CCSET2") (class "Default")
      (node (ref "C21") (pin "1") (pinfunction "1_1") (pintype "passive"))
      (node (ref "R36") (pin "2") (pinfunction "2_2") (pintype "passive"))
      (node (ref "U7") (pin "3") (pinfunction "VIN+_3") (pintype "bidirectional"))
    )
    (net (code "21") (name "C1CCSET3") (class "Default")
      (node (ref "C8") (pin "1") (pinfunction "1_1") (pintype "passive"))
      (node (ref "R28") (pin "2") (pinfunction "2_2") (pintype "passive"))
      (node (ref "U3") (pin "3") (pinfunction "VIN+_3") (pintype "bidirectional"))
    )
    (net (code "22") (name "C1CCSET4") (class "Default")
      (node (ref "C31") (pin "1") (pinfunction "1_1") (pintype "passive"))
      (node (ref "R61") (pin "2") (pinfunction "2_2") (pintype "passive"))
      (node (ref "U13") (pin "3") (pinfunction "VIN+_3") (pintype "bidirectional"))
    )
    (net (code "23") (name "C1DFB1") (class "Default")
      (node (ref "Q2") (pin "3") (pinfunction "S_3") (pintype "bidirectional"))
      (node (ref "R2") (pin "1") (pinfunction "1_1") (pintype "passive"))
      (node (ref "R54") (pin "1") (pinfunction "1_1") (pintype "passive"))
    )
    (net (code "24") (name "C1DFB2") (class "Default")
      (node (ref "Q4") (pin "3") (pinfunction "S_3") (pintype "bidirectional"))
      (node (ref "R1") (pin "1") (pinfunction "1_1") (pintype "passive"))
      (node (ref "R38") (pin "1") (pinfunction "1_1") (pintype "passive"))
    )
    (net (code "25") (name "C1DFB3") (class "Default")
      (node (ref "Q5") (pin "3") (pinfunction "S_3") (pintype "bidirectional"))
      (node (ref "R23") (pin "1") (pinfunction "1_1") (pintype "passive"))
      (node (ref "R29") (pin "1") (pinfunction "1_1") (pintype "passive"))
    )
    (net (code "26") (name "C1DFB4") (class "Default")
      (node (ref "Q6") (pin "3") (pinfunction "S_3") (pintype "bidirectional"))
      (node (ref "R24") (pin "1") (pinfunction "1_1") (pintype "passive"))
      (node (ref "R63") (pin "1") (pinfunction "1_1") (pintype "passive"))
    )
    (net (code "27") (name "C1DOFF") (class "Default")
      (node (ref "D4") (pin "A") (pinfunction "ANODE_A") (pintype "passive"))
      (node (ref "Q3") (pin "3") (pinfunction "D_3") (pintype "bidirectional"))
      (node (ref "R58") (pin "2") (pinfunction "2_2") (pintype "passive"))
    )
    (net (code "28") (name "C1DOFFG") (class "Default")
      (node (ref "Q3") (pin "1") (pinfunction "G_1") (pintype "bidirectional"))
      (node (ref "U17") (pin "B15") (pinfunction "B15_B15") (pintype "bidirectional"))
    )
    (net (code "29") (name "C1FET") (class "Default")
      (node (ref "Q1") (pin "4") (pinfunction "G_4") (pintype "bidirectional"))
      (node (ref "Q10") (pin "2") (pinfunction "E_2") (pintype "bidirectional"))
      (node (ref "Q11") (pin "2") (pinfunction "E_2") (pintype "bidirectional"))
      (node (ref "Q7") (pin "4") (pinfunction "G_4") (pintype "bidirectional"))
      (node (ref "Q8") (pin "4") (pinfunction "G_4") (pintype "bidirectional"))
    )
    (net (code "30") (name "C1NGATE1") (class "Default")
      (node (ref "C23") (pin "2") (pinfunction "2_2") (pintype "passive"))
      (node (ref "R43") (pin "2") (pinfunction "2_2") (pintype "passive"))
      (node (ref "R59") (pin "1") (pinfunction "1_1") (pintype "passive"))
      (node (ref "U8") (pin "1") (pinfunction "VOUT_1") (pintype "bidirectional"))
    )
    (net (code "31") (name "C1NGATE2") (class "Default")
      (node (ref "C12") (pin "2") (pinfunction "2_2") (pintype "passive"))
      (node (ref "R51") (pin "1") (pinfunction "1_1") (pintype "passive"))
      (node (ref "R8") (pin "2") (pinfunction "2_2") (pintype "passive"))
      (node (ref "U7") (pin "1") (pinfunction "VOUT_1") (pintype "bidirectional"))
    )
    (net (code "32") (name "C1NGATE3") (class "Default")
      (node (ref "C5") (pin "2") (pinfunction "2_2") (pintype "passive"))
      (node (ref "R27") (pin "2") (pinfunction "2_2") (pintype "passive"))
      (node (ref "R35") (pin "1") (pinfunction "1_1") (pintype "passive"))
      (node (ref "U3") (pin "1") (pinfunction "VOUT_1") (pintype "bidirectional"))
    )
    (net (code "33") (name "C1NGATE4") (class "Default")
      (node (ref "C15") (pin "2") (pinfunction "2_2") (pintype "passive"))
      (node (ref "R26") (pin "2") (pinfunction "2_2") (pintype "passive"))
      (node (ref "R50") (pin "1") (pinfunction "1_1") (pintype "passive"))
      (node (ref "U13") (pin "1") (pinfunction "VOUT_1") (pintype "bidirectional"))
    )
    (net (code "34") (name "C1ON") (class "Default")
      (node (ref "Q14") (pin "1") (pinfunction "G_1") (pintype "bidirectional"))
      (node (ref "R72") (pin "1") (pinfunction "1_1") (pintype "passive"))
      (node (ref "U17") (pin "B14") (pinfunction "B14_B14") (pintype "bidirectional"))
    )
    (net (code "35") (name "C1R") (class "Default")
      (node (ref "R37") (pin "1") (pinfunction "1_1") (pintype "passive"))
      (node (ref "R39") (pin "2") (pinfunction "2_2") (pintype "passive"))
      (node (ref "U17") (pin "A1") (pinfunction "A1_A1") (pintype "bidirectional"))
    )
    (net (code "36") (name "C1TH") (class "Default")
      (node (ref "C39") (pin "1") (pinfunction "1_1") (pintype "passive"))
      (node (ref "J4") (pin "2") (pinfunction "2_2") (pintype "passive"))
      (node (ref "R7") (pin "1") (pinfunction "1_1") (pintype "passive"))
      (node (ref "U17") (pin "A3") (pinfunction "A3_A3") (pintype "bidirectional"))
    )
    (net (code "37") (name "C1V") (class "Default")
      (node (ref "C33") (pin "1") (pinfunction "1_1") (pintype "passive"))
      (node (ref "R16") (pin "2") (pinfunction "2_2") (pintype "passive"))
      (node (ref "U17") (pin "B0") (pinfunction "B0_B0") (pintype "bidirectional"))
    )
    (net (code "38") (name "C1V_HI") (class "Default")
      (node (ref "C51") (pin "1") (pinfunction "1_1") (pintype "passive"))
      (node (ref "R82") (pin "2") (pinfunction "2_2") (pintype "passive"))
      (node (ref "U17") (pin "A6") (pinfunction "A6_A6") (pintype "bidirectional"))
    )
    (net (code "39") (name "C2DOFF") (class "Default")
      (node (ref "D11") (pin "A") (pinfunction "ANODE_A") (pintype "passive"))
      (node (ref "D2") (pin "A") (pinfunction "ANODE_A") (pintype "passive"))
      (node (ref "D3") (pin "A") (pinfunction "ANODE_A") (pintype "passive"))
      (node (ref "Q15") (pin "3") (pinfunction "D_3") (pintype "bidirectional"))
      (node (ref "R33") (pin "2") (pinfunction "2_2") (pintype "passive"))
      (node (ref "R47") (pin "2") (pinfunction "2_2") (pintype "passive"))
      (node (ref "R78") (pin "2") (pinfunction "2_2") (pintype "passive"))
    )
    (net (code "40") (name "C2DOFFG") (class "Default")
      (node (ref "Q15") (pin "1") (pinfunction "G_1") (pintype "bidirectional"))
      (node (ref "U17") (pin "A15") (pinfunction "A15_A15") (pintype "bidirectional"))
    )
    (net (code "41") (name "C2TH") (class "Default")
      (node (ref "U17") (pin "A2") (pinfunction "A2_A2") (pintype "bidirectional"))
    )
    (net (code "42") (name "DI") (class "Default")
      (node (ref "Q16") (pin "1") (pinfunction "G_1") (pintype "bidirectional"))
      (node (ref "U17") (pin "B13") (pinfunction "B13_B13") (pintype "bidirectional"))
    )
    (net (code "43") (name "DI2") (class "Default")
      (node (ref "JP1") (pin "2") (pinfunction "2_2") (pintype "passive"))
      (node (ref "LED7") (pin "2-DOUT") (pinfunction "DOUT_2-DOUT") (pintype "output"))
    )
    (net (code "44") (name "FANON") (class "Default")
      (node (ref "Q9") (pin "1") (pinfunction "G_1") (pintype "bidirectional"))
      (node (ref "R34") (pin "2") (pinfunction "2_2") (pintype "passive"))
      (node (ref "U17") (pin "B4") (pinfunction "B4_B4") (pintype "bidirectional"))
    )
    (net (code "45") (name "GND") (class "Default")
      (node (ref "C10") (pin "2") (pinfunction "2_2") (pintype "passive"))
      (node (ref "C11") (pin "2") (pinfunction "2_2") (pintype "passive"))
      (node (ref "C13") (pin "2") (pinfunction "2_2") (pintype "passive"))
      (node (ref "C14") (pin "2") (pinfunction "2_2") (pintype "passive"))
      (node (ref "C16") (pin "2") (pinfunction "2_2") (pintype "passive"))
      (node (ref "C17") (pin "2") (pinfunction "2_2") (pintype "passive"))
      (node (ref "C18") (pin "2") (pinfunction "2_2") (pintype "passive"))
      (node (ref "C19") (pin "2") (pinfunction "2_2") (pintype "passive"))
      (node (ref "C2") (pin "2") (pinfunction "2_2") (pintype "passive"))
      (node (ref "C20") (pin "2") (pinfunction "2_2") (pintype "passive"))
      (node (ref "C21") (pin "2") (pinfunction "2_2") (pintype "passive"))
      (node (ref "C22") (pin "2") (pinfunction "2_2") (pintype "passive"))
      (node (ref "C24") (pin "2") (pinfunction "2_2") (pintype "passive"))
      (node (ref "C26") (pin "-") (pinfunction "-_-") (pintype "passive"))
      (node (ref "C27") (pin "2") (pinfunction "2_2") (pintype "passive"))
      (node (ref "C28") (pin "2") (pinfunction "2_2") (pintype "passive"))
      (node (ref "C29") (pin "2") (pinfunction "2_2") (pintype "passive"))
      (node (ref "C3") (pin "2") (pinfunction "2_2") (pintype "passive"))
      (node (ref "C30") (pin "2") (pinfunction "2_2") (pintype "passive"))
      (node (ref "C31") (pin "2") (pinfunction "2_2") (pintype "passive"))
      (node (ref "C32") (pin "-") (pinfunction "-_-") (pintype "passive"))
      (node (ref "C33") (pin "2") (pinfunction "2_2") (pintype "passive"))
      (node (ref "C34") (pin "2") (pinfunction "2_2") (pintype "passive"))
      (node (ref "C35") (pin "2") (pinfunction "2_2") (pintype "passive"))
      (node (ref "C37") (pin "2") (pinfunction "2_2") (pintype "passive"))
      (node (ref "C38") (pin "2") (pinfunction "2_2") (pintype "passive"))
      (node (ref "C39") (pin "2") (pinfunction "2_2") (pintype "passive"))
      (node (ref "C4") (pin "2") (pinfunction "2_2") (pintype "passive"))
      (node (ref "C41") (pin "2") (pinfunction "2_2") (pintype "passive"))
      (node (ref "C42") (pin "2") (pinfunction "2_2") (pintype "passive"))
      (node (ref "C43") (pin "2") (pinfunction "2_2") (pintype "passive"))
      (node (ref "C45") (pin "2") (pinfunction "2_2") (pintype "passive"))
      (node (ref "C46") (pin "2") (pinfunction "2_2") (pintype "passive"))
      (node (ref "C50") (pin "2") (pinfunction "2_2") (pintype "passive"))
      (node (ref "C51") (pin "2") (pinfunction "2_2") (pintype "passive"))
      (node (ref "C6") (pin "2") (pinfunction "2_2") (pintype "passive"))
      (node (ref "C7") (pin "-") (pinfunction "-_-") (pintype "passive"))
      (node (ref "C8") (pin "2") (pinfunction "2_2") (pintype "passive"))
      (node (ref "C9") (pin "2") (pinfunction "2_2") (pintype "passive"))
      (node (ref "D9") (pin "A") (pinfunction "ANODE_A") (pintype "passive"))
      (node (ref "J1") (pin "1") (pinfunction "1_1") (pintype "passive"))
      (node (ref "J4") (pin "1") (pinfunction "1_1") (pintype "passive"))
      (node (ref "J5") (pin "S2") (pinfunction "S2_S2") (pintype "bidirectional"))
      (node (ref "J6") (pin "1") (pinfunction "1_1") (pintype "passive"))
      (node (ref "JP1") (pin "1") (pinfunction "1_1") (pintype "passive"))
      (node (ref "LED7") (pin "3-GND") (pinfunction "GND_3-GND") (pintype "bidirectional"))
      (node (ref "Q1") (pin "1") (pinfunction "S_1") (pintype "bidirectional"))
      (node (ref "Q1") (pin "2") (pinfunction "S_2") (pintype "bidirectional"))
      (node (ref "Q1") (pin "3") (pinfunction "S_3") (pintype "bidirectional"))
      (node (ref "Q11") (pin "3") (pinfunction "C_3") (pintype "bidirectional"))
      (node (ref "Q13") (pin "3") (pinfunction "C_3") (pintype "bidirectional"))
      (node (ref "Q14") (pin "2") (pinfunction "S_2") (pintype "bidirectional"))
      (node (ref "Q15") (pin "2") (pinfunction "S_2") (pintype "bidirectional"))
      (node (ref "Q16") (pin "2") (pinfunction "S_2") (pintype "bidirectional"))
      (node (ref "Q3") (pin "2") (pinfunction "S_2") (pintype "bidirectional"))
      (node (ref "Q7") (pin "1") (pinfunction "S_1") (pintype "bidirectional"))
      (node (ref "Q7") (pin "2") (pinfunction "S_2") (pintype "bidirectional"))
      (node (ref "Q7") (pin "3") (pinfunction "S_3") (pintype "bidirectional"))
      (node (ref "Q8") (pin "1") (pinfunction "S_1") (pintype "bidirectional"))
      (node (ref "Q8") (pin "2") (pinfunction "S_2") (pintype "bidirectional"))
      (node (ref "Q8") (pin "3") (pinfunction "S_3") (pintype "bidirectional"))
      (node (ref "Q9") (pin "2") (pinfunction "S_2") (pintype "bidirectional"))
      (node (ref "R1") (pin "2") (pinfunction "2_2") (pintype "passive"))
      (node (ref "R11") (pin "2") (pinfunction "2_2") (pintype "passive"))
      (node (ref "R13") (pin "1") (pinfunction "1_1") (pintype "passive"))
      (node (ref "R19") (pin "1") (pinfunction "1_1") (pintype "passive"))
      (node (ref "R2") (pin "2") (pinfunction "2_2") (pintype "passive"))
      (node (ref "R23") (pin "2") (pinfunction "2_2") (pintype "passive"))
      (node (ref "R24") (pin "2") (pinfunction "2_2") (pintype "passive"))
      (node (ref "R32") (pin "1") (pinfunction "1_1") (pintype "passive"))
      (node (ref "R34") (pin "1") (pinfunction "1_1") (pintype "passive"))
      (node (ref "R35") (pin "2") (pinfunction "2_2") (pintype "passive"))
      (node (ref "R39") (pin "1") (pinfunction "1_1") (pintype "passive"))
      (node (ref "R4") (pin "2") (pinfunction "2_2") (pintype "passive"))
      (node (ref "R46") (pin "1") (pinfunction "1_1") (pintype "passive"))
      (node (ref "R50") (pin "2") (pinfunction "2_2") (pintype "passive"))
      (node (ref "R51") (pin "2") (pinfunction "2_2") (pintype "passive"))
      (node (ref "R57") (pin "1") (pinfunction "1_1") (pintype "passive"))
      (node (ref "R59") (pin "2") (pinfunction "2_2") (pintype "passive"))
      (node (ref "R65") (pin "1") (pinfunction "1_1") (pintype "passive"))
      (node (ref "R68") (pin "1") (pinfunction "1_1") (pintype "passive"))
      (node (ref "R69") (pin "2") (pinfunction "2_2") (pintype "passive"))
      (node (ref "R72") (pin "2") (pinfunction "2_2") (pintype "passive"))
      (node (ref "R74") (pin "2") (pinfunction "2_2") (pintype "passive"))
      (node (ref "R76") (pin "1") (pinfunction "1_1") (pintype "passive"))
      (node (ref "R80") (pin "2") (pinfunction "2_2") (pintype "passive"))
      (node (ref "R84") (pin "1") (pinfunction "1_1") (pintype "passive"))
      (node (ref "R94") (pin "1") (pinfunction "1_1") (pintype "passive"))
      (node (ref "S1") (pin "3") (pinfunction "3_3") (pintype "passive"))
      (node (ref "S1") (pin "4") (pinfunction "4_4") (pintype "passive"))
      (node (ref "S2") (pin "3") (pinfunction "3_3") (pintype "passive"))
      (node (ref "S2") (pin "4") (pinfunction "4_4") (pintype "passive"))
      (node (ref "T1") (pin "1") (pinfunction "1_1") (pintype "bidirectional"))
      (node (ref "T2") (pin "1") (pinfunction "1_1") (pintype "bidirectional"))
      (node (ref "U1") (pin "2") (pinfunction "GND_2") (pintype "bidirectional"))
      (node (ref "U11") (pin "4") (pinfunction "GND_4") (pintype "power_in"))
      (node (ref "U13") (pin "2") (pinfunction "VSS_2") (pintype "bidirectional"))
      (node (ref "U15") (pin "2") (pinfunction "GND_2") (pintype "bidirectional"))
      (node (ref "U16") (pin "2") (pinfunction "GND_2") (pintype "bidirectional"))
      (node (ref "U16") (pin "2@1") (pinfunction "GND_2@1") (pintype "bidirectional"))
      (node (ref "U17") (pin "GND") (pinfunction "GND_GND") (pintype "bidirectional"))
      (node (ref "U17") (pin "GND2") (pinfunction "GND2_GND2") (pintype "bidirectional"))
      (node (ref "U17") (pin "GND4") (pinfunction "GND4_GND4") (pintype "bidirectional"))
      (node (ref "U18") (pin "2") (pinfunction "GND_2") (pintype "bidirectional"))
      (node (ref "U2") (pin "4") (pinfunction "GND_4") (pintype "bidirectional"))
      (node (ref "U3") (pin "2") (pinfunction "VSS_2") (pintype "bidirectional"))
      (node (ref "U5") (pin "2") (pinfunction "GND_2") (pintype "bidirectional"))
      (node (ref "U6") (pin "3") (pinfunction "A_3") (pintype "passive"))
      (node (ref "U7") (pin "2") (pinfunction "VSS_2") (pintype "bidirectional"))
      (node (ref "U8") (pin "2") (pinfunction "VSS_2") (pintype "bidirectional"))
      (node (ref "U9") (pin "2") (pinfunction "GND_2") (pintype "bidirectional"))
    )
    (net (code "46") (name "HIN") (class "Default")
      (node (ref "R42") (pin "1") (pinfunction "1_1") (pintype "passive"))
      (node (ref "U2") (pin "2") (pinfunction "HIN_2") (pintype "bidirectional"))
    )
    (net (code "47") (name "HSTH") (class "Default")
      (node (ref "C41") (pin "1") (pinfunction "1_1") (pintype "passive"))
      (node (ref "R77") (pin "1") (pinfunction "1_1") (pintype "passive"))
      (node (ref "T1") (pin "2") (pinfunction "2_2") (pintype "bidirectional"))
      (node (ref "U18") (pin "1") (pinfunction "2_1") (pintype "bidirectional"))
    )
    (net (code "48") (name "HSTH2") (class "Default")
      (node (ref "C43") (pin "1") (pinfunction "1_1") (pintype "passive"))
      (node (ref "R14") (pin "1") (pinfunction "1_1") (pintype "passive"))
      (node (ref "T2") (pin "2") (pinfunction "2_2") (pintype "bidirectional"))
      (node (ref "U15") (pin "3") (pinfunction "1_3") (pintype "bidirectional"))
    )
    (net (code "49") (name "ISNS_REF") (class "Default")
      (node (ref "C11") (pin "1") (pinfunction "1_1") (pintype "passive"))
      (node (ref "C17") (pin "1") (pinfunction "1_1") (pintype "passive"))
      (node (ref "C28") (pin "1") (pinfunction "1_1") (pintype "passive"))
      (node (ref "R10") (pin "2") (pinfunction "2_2") (pintype "passive"))
      (node (ref "R11") (pin "1") (pinfunction "1_1") (pintype "passive"))
      (node (ref "TP5") (pin "1") (pinfunction "1_1") (pintype "bidirectional"))
      (node (ref "U1") (pin "1") (pinfunction "REF_1") (pintype "bidirectional"))
      (node (ref "U17") (pin "A5") (pinfunction "A5_A5") (pintype "bidirectional"))
      (node (ref "U9") (pin "1") (pinfunction "REF_1") (pintype "bidirectional"))
    )
    (net (code "50") (name "LIN_N") (class "Default")
      (node (ref "R45") (pin "1") (pinfunction "1_1") (pintype "passive"))
      (node (ref "U2") (pin "3") (pinfunction "/LIN_3") (pintype "bidirectional"))
    )
    (net (code "51") (name "Net-(C5-Pad1)") (class "Default")
      (node (ref "C5") (pin "1") (pinfunction "1_1") (pintype "passive"))
      (node (ref "R30") (pin "2") (pinfunction "2_2") (pintype "passive"))
    )
    (net (code "52") (name "Net-(C12-Pad1)") (class "Default")
      (node (ref "C12") (pin "1") (pinfunction "1_1") (pintype "passive"))
      (node (ref "R40") (pin "2") (pinfunction "2_2") (pintype "passive"))
    )
    (net (code "53") (name "Net-(C15-Pad1)") (class "Default")
      (node (ref "C15") (pin "1") (pinfunction "1_1") (pintype "passive"))
      (node (ref "R64") (pin "2") (pinfunction "2_2") (pintype "passive"))
    )
    (net (code "54") (name "Net-(C23-Pad1)") (class "Default")
      (node (ref "C23") (pin "1") (pinfunction "1_1") (pintype "passive"))
      (node (ref "R55") (pin "2") (pinfunction "2_2") (pintype "passive"))
    )
    (net (code "55") (name "Net-(D1-CATHODE)") (class "Default")
      (node (ref "C1") (pin "1") (pinfunction "1_1") (pintype "passive"))
      (node (ref "D1") (pin "K") (pinfunction "CATHODE_K") (pintype "passive"))
      (node (ref "U2") (pin "8") (pinfunction "VB_8") (pintype "bidirectional"))
    )
    (net (code "56") (name "Net-(D2-CATHODE)") (class "Default")
      (node (ref "D2") (pin "K") (pinfunction "CATHODE_K") (pintype "passive"))
      (node (ref "R29") (pin "2") (pinfunction "2_2") (pintype "passive"))
      (node (ref "R30") (pin "1") (pinfunction "1_1") (pintype "passive"))
      (node (ref "U3") (pin "4") (pinfunction "VIN-_4") (pintype "bidirectional"))
    )
    (net (code "57") (name "Net-(D3-CATHODE)") (class "Default")
      (node (ref "D3") (pin "K") (pinfunction "CATHODE_K") (pintype "passive"))
      (node (ref "R38") (pin "2") (pinfunction "2_2") (pintype "passive"))
      (node (ref "R40") (pin "1") (pinfunction "1_1") (pintype "passive"))
      (node (ref "U7") (pin "4") (pinfunction "VIN-_4") (pintype "bidirectional"))
    )
    (net (code "58") (name "Net-(D4-CATHODE)") (class "Default")
      (node (ref "D4") (pin "K") (pinfunction "CATHODE_K") (pintype "passive"))
      (node (ref "R54") (pin "2") (pinfunction "2_2") (pintype "passive"))
      (node (ref "R55") (pin "1") (pinfunction "1_1") (pintype "passive"))
      (node (ref "U8") (pin "4") (pinfunction "VIN-_4") (pintype "bidirectional"))
    )
    (net (code "59") (name "Net-(D5-ANODE)") (class "Default")
      (node (ref "D5") (pin "A") (pinfunction "ANODE_A") (pintype "passive"))
      (node (ref "R6") (pin "2") (pinfunction "2_2") (pintype "passive"))
    )
    (net (code "60") (name "Net-(D5-CATHODE)") (class "Default")
      (node (ref "D5") (pin "K") (pinfunction "CATHODE_K") (pintype "passive"))
      (node (ref "Q10") (pin "1") (pinfunction "B_1") (pintype "bidirectional"))
      (node (ref "Q11") (pin "1") (pinfunction "B_1") (pintype "bidirectional"))
      (node (ref "R49") (pin "1") (pinfunction "1_1") (pintype "passive"))
    )
    (net (code "61") (name "Net-(D11-CATHODE)") (class "Default")
      (node (ref "D11") (pin "K") (pinfunction "CATHODE_K") (pintype "passive"))
      (node (ref "R63") (pin "2") (pinfunction "2_2") (pintype "passive"))
      (node (ref "R64") (pin "1") (pinfunction "1_1") (pintype "passive"))
      (node (ref "U13") (pin "4") (pinfunction "VIN-_4") (pintype "bidirectional"))
    )
    (net (code "62") (name "Net-(J1-Pad2)") (class "Default")
      (node (ref "J1") (pin "2") (pinfunction "2_2") (pintype "passive"))
      (node (ref "R22") (pin "1") (pinfunction "1_1") (pintype "passive"))
    )
    (net (code "63") (name "Net-(L2-P$1)") (class "Default")
      (node (ref "C1") (pin "2") (pinfunction "2_2") (pintype "passive"))
      (node (ref "J5") (pin "D2") (pinfunction "D2_D2") (pintype "bidirectional"))
      (node (ref "J5") (pin "S1") (pinfunction "S1_S1") (pintype "bidirectional"))
      (node (ref "L2") (pin "1") (pinfunction "P$1_1") (pintype "passive"))
      (node (ref "U2") (pin "6") (pinfunction "VS_6") (pintype "bidirectional"))
    )
    (net (code "64") (name "Net-(L2-P$2)") (class "Default")
      (node (ref "C18") (pin "1") (pinfunction "1_1") (pintype "passive"))
      (node (ref "C26") (pin "+") (pinfunction "+_+") (pintype "passive"))
      (node (ref "L2") (pin "2") (pinfunction "P$2_2") (pintype "passive"))
      (node (ref "L4") (pin "1") (pinfunction "P$1_1") (pintype "passive"))
    )
    (net (code "65") (name "Net-(L3-P$1)") (class "Default")
      (node (ref "C25") (pin "2") (pinfunction "2_2") (pintype "passive"))
      (node (ref "L3") (pin "1") (pinfunction "P$1_1") (pintype "passive"))
      (node (ref "U5") (pin "6") (pinfunction "SW_6") (pintype "bidirectional"))
    )
    (net (code "66") (name "Net-(LED7-DIN)") (class "Default")
      (node (ref "LED7") (pin "4-DIN") (pinfunction "DIN_4-DIN") (pintype "input"))
      (node (ref "Q16") (pin "3") (pinfunction "D_3") (pintype "bidirectional"))
      (node (ref "R41") (pin "2") (pinfunction "2_2") (pintype "passive"))
    )
    (net (code "67") (name "Net-(Q2-G)") (class "Default")
      (node (ref "Q2") (pin "1") (pinfunction "G_1") (pintype "bidirectional"))
      (node (ref "R43") (pin "1") (pinfunction "1_1") (pintype "passive"))
    )
    (net (code "68") (name "Net-(Q4-G)") (class "Default")
      (node (ref "Q4") (pin "1") (pinfunction "G_1") (pintype "bidirectional"))
      (node (ref "R8") (pin "1") (pinfunction "1_1") (pintype "passive"))
    )
    (net (code "69") (name "Net-(Q5-G)") (class "Default")
      (node (ref "Q5") (pin "1") (pinfunction "G_1") (pintype "bidirectional"))
      (node (ref "R27") (pin "1") (pinfunction "1_1") (pintype "passive"))
    )
    (net (code "70") (name "Net-(Q6-G)") (class "Default")
      (node (ref "Q6") (pin "1") (pinfunction "G_1") (pintype "bidirectional"))
      (node (ref "R26") (pin "1") (pinfunction "1_1") (pintype "passive"))
    )
    (net (code "71") (name "Net-(Q9-D)") (class "Default")
      (node (ref "J2") (pin "2") (pinfunction "2_2") (pintype "passive"))
      (node (ref "Q9") (pin "3") (pinfunction "D_3") (pintype "bidirectional"))
    )
    (net (code "72") (name "Net-(Q12-B)") (class "Default")
      (node (ref "Q12") (pin "1") (pinfunction "B_1") (pintype "bidirectional"))
      (node (ref "Q13") (pin "1") (pinfunction "B_1") (pintype "bidirectional"))
      (node (ref "R66") (pin "1") (pinfunction "1_1") (pintype "passive"))
    )
    (net (code "73") (name "Net-(Q12-E)") (class "Default")
      (node (ref "Q12") (pin "2") (pinfunction "E_2") (pintype "bidirectional"))
      (node (ref "Q13") (pin "2") (pinfunction "E_2") (pintype "bidirectional"))
      (node (ref "R49") (pin "2") (pinfunction "2_2") (pintype "passive"))
      (node (ref "R6") (pin "1") (pinfunction "1_1") (pintype "passive"))
    )
    (net (code "74") (name "Net-(Q14-D)") (class "Default")
      (node (ref "Q14") (pin "3") (pinfunction "D_3") (pintype "bidirectional"))
      (node (ref "R60") (pin "2") (pinfunction "2_2") (pintype "passive"))
      (node (ref "R66") (pin "2") (pinfunction "2_2") (pintype "passive"))
    )
    (net (code "75") (name "Net-(R28-Pad1)") (class "Default")
      (node (ref "R28") (pin "1") (pinfunction "1_1") (pintype "passive"))
      (node (ref "R31") (pin "2") (pinfunction "2_2") (pintype "passive"))
      (node (ref "R32") (pin "2") (pinfunction "2_2") (pintype "passive"))
    )
    (net (code "76") (name "Net-(R36-Pad1)") (class "Default")
      (node (ref "R36") (pin "1") (pinfunction "1_1") (pintype "passive"))
      (node (ref "R44") (pin "2") (pinfunction "2_2") (pintype "passive"))
      (node (ref "R46") (pin "2") (pinfunction "2_2") (pintype "passive"))
    )
    (net (code "77") (name "Net-(R52-Pad1)") (class "Default")
      (node (ref "R52") (pin "1") (pinfunction "1_1") (pintype "passive"))
      (node (ref "R56") (pin "2") (pinfunction "2_2") (pintype "passive"))
      (node (ref "R57") (pin "2") (pinfunction "2_2") (pintype "passive"))
    )
    (net (code "78") (name "Net-(R61-Pad1)") (class "Default")
      (node (ref "R61") (pin "1") (pinfunction "1_1") (pintype "passive"))
      (node (ref "R62") (pin "2") (pinfunction "2_2") (pintype "passive"))
      (node (ref "R65") (pin "2") (pinfunction "2_2") (pintype "passive"))
    )
    (net (code "79") (name "Net-(R83-Pad2)") (class "Default")
      (node (ref "R83") (pin "2") (pinfunction "2_2") (pintype "passive"))
      (node (ref "R84") (pin "2") (pinfunction "2_2") (pintype "passive"))
      (node (ref "R85") (pin "1") (pinfunction "1_1") (pintype "passive"))
    )
    (net (code "80") (name "Net-(U1-OUT)") (class "Default")
      (node (ref "R12") (pin "1") (pinfunction "1_1") (pintype "passive"))
      (node (ref "U1") (pin "6") (pinfunction "OUT_6") (pintype "bidirectional"))
    )
    (net (code "81") (name "Net-(U1-VCC)") (class "Default")
      (node (ref "C14") (pin "1") (pinfunction "1_1") (pintype "passive"))
      (node (ref "R73") (pin "2") (pinfunction "2_2") (pintype "passive"))
      (node (ref "U1") (pin "3") (pinfunction "VCC_3") (pintype "bidirectional"))
    )
    (net (code "82") (name "Net-(U2-HO)") (class "Default")
      (node (ref "R17") (pin "1") (pinfunction "1_1") (pintype "passive"))
      (node (ref "U2") (pin "7") (pinfunction "HO_7") (pintype "bidirectional"))
    )
    (net (code "83") (name "Net-(U2-LO)") (class "Default")
      (node (ref "R3") (pin "1") (pinfunction "1_1") (pintype "passive"))
      (node (ref "U2") (pin "5") (pinfunction "LO_5") (pintype "bidirectional"))
    )
    (net (code "84") (name "Net-(U5-BST)") (class "Default")
      (node (ref "C25") (pin "1") (pinfunction "1_1") (pintype "passive"))
      (node (ref "U5") (pin "1") (pinfunction "BST_1") (pintype "bidirectional"))
    )
    (net (code "85") (name "Net-(U5-EN)") (class "Default")
      (node (ref "R95") (pin "1") (pinfunction "1_1") (pintype "passive"))
      (node (ref "U5") (pin "4") (pinfunction "EN_4") (pintype "bidirectional"))
    )
    (net (code "86") (name "Net-(U5-FB)") (class "Default")
      (node (ref "R93") (pin "1") (pinfunction "1_1") (pintype "passive"))
      (node (ref "R94") (pin "2") (pinfunction "2_2") (pintype "passive"))
      (node (ref "U5") (pin "3") (pinfunction "FB_3") (pintype "bidirectional"))
    )
    (net (code "87") (name "Net-(U9-OUT)") (class "Default")
      (node (ref "R70") (pin "1") (pinfunction "1_1") (pintype "passive"))
      (node (ref "U9") (pin "6") (pinfunction "OUT_6") (pintype "bidirectional"))
    )
    (net (code "88") (name "Net-(U9-VCC)") (class "Default")
      (node (ref "C19") (pin "1") (pinfunction "1_1") (pintype "passive"))
      (node (ref "R71") (pin "1") (pinfunction "1_1") (pintype "passive"))
      (node (ref "U9") (pin "3") (pinfunction "VCC_3") (pintype "bidirectional"))
    )
    (net (code "89") (name "Net-(U11A-VIN+)") (class "Default")
      (node (ref "R79") (pin "2") (pinfunction "2_2") (pintype "passive"))
      (node (ref "R81") (pin "1") (pinfunction "1_1") (pintype "passive"))
      (node (ref "U11") (pin "3") (pinfunction "VIN+_3") (pintype "bidirectional"))
    )
    (net (code "90") (name "Net-(U11A-VIN-)") (class "Default")
      (node (ref "R75") (pin "2") (pinfunction "2_2") (pintype "passive"))
      (node (ref "R76") (pin "2") (pinfunction "2_2") (pintype "passive"))
      (node (ref "U11") (pin "2") (pinfunction "VIN-_2") (pintype "bidirectional"))
    )
    (net (code "91") (name "Net-(U11A-VOUT)") (class "Default")
      (node (ref "R81") (pin "2") (pinfunction "2_2") (pintype "passive"))
      (node (ref "R82") (pin "1") (pinfunction "1_1") (pintype "passive"))
      (node (ref "U11") (pin "1") (pinfunction "VOUT_1") (pintype "bidirectional"))
    )
    (net (code "92") (name "Net-(U11B-VIN+)") (class "Default")
      (node (ref "R20") (pin "2") (pinfunction "2_2") (pintype "passive"))
      (node (ref "R21") (pin "1") (pinfunction "1_1") (pintype "passive"))
      (node (ref "U11") (pin "5") (pinfunction "VIN+_5") (pintype "bidirectional"))
    )
    (net (code "93") (name "Net-(U11B-VIN-)") (class "Default")
      (node (ref "R18") (pin "2") (pinfunction "2_2") (pintype "passive"))
      (node (ref "R19") (pin "2") (pinfunction "2_2") (pintype "passive"))
      (node (ref "U11") (pin "6") (pinfunction "VIN-_6") (pintype "bidirectional"))
    )
    (net (code "94") (name "Net-(U11B-VOUT)") (class "Default")
      (node (ref "R16") (pin "1") (pinfunction "1_1") (pintype "passive"))
      (node (ref "R21") (pin "2") (pinfunction "2_2") (pintype "passive"))
      (node (ref "U11") (pin "7") (pinfunction "VOUT_7") (pintype "bidirectional"))
    )
    (net (code "95") (name "Net-(U17-A12{slash}D+)") (class "Default")
      (node (ref "R53") (pin "2") (pinfunction "2_2") (pintype "passive"))
      (node (ref "U17") (pin "A12") (pinfunction "A12/D+_A12") (pintype "bidirectional"))
    )
    (net (code "96") (name "OA1+") (class "Default")
      (node (ref "JP3") (pin "2") (pinfunction "2_2") (pintype "passive"))
      (node (ref "R18") (pin "1") (pinfunction "1_1") (pintype "passive"))
      (node (ref "R75") (pin "1") (pinfunction "1_1") (pintype "passive"))
    )
    (net (code "97") (name "OA1-") (class "Default")
      (node (ref "JP2") (pin "2") (pinfunction "2_2") (pintype "passive"))
      (node (ref "R20") (pin "1") (pinfunction "1_1") (pintype "passive"))
      (node (ref "R79") (pin "1") (pinfunction "1_1") (pintype "passive"))
    )
    (net (code "98") (name "PA8") (class "Default")
      (node (ref "R42") (pin "2") (pinfunction "2_2") (pintype "passive"))
      (node (ref "R80") (pin "1") (pinfunction "1_1") (pintype "passive"))
      (node (ref "U17") (pin "A8") (pinfunction "A8_A8") (pintype "bidirectional"))
    )
    (net (code "99") (name "PA9") (class "Default")
      (node (ref "R4") (pin "1") (pinfunction "1_1") (pintype "passive"))
      (node (ref "R45") (pin "2") (pinfunction "2_2") (pintype "passive"))
      (node (ref "U17") (pin "A9") (pinfunction "A9_A9") (pintype "bidirectional"))
    )
    (net (code "100") (name "PB5") (class "Default")
      (node (ref "U15") (pin "6") (pinfunction "SEL_6") (pintype "bidirectional"))
      (node (ref "U17") (pin "B5") (pinfunction "B5_B5") (pintype "bidirectional"))
    )
    (net (code "101") (name "PB8") (class "Default")
      (node (ref "U17") (pin "B8") (pinfunction "B8_B8") (pintype "bidirectional"))
    )
    (net (code "102") (name "PB12") (class "Default")
      (node (ref "U17") (pin "B12") (pinfunction "B12_B12") (pintype "bidirectional"))
      (node (ref "U18") (pin "6") (pinfunction "SEL_6") (pintype "bidirectional"))
    )
    (net (code "103") (name "RS+") (class "Default")
      (node (ref "J3") (pin "2") (pinfunction "2_2") (pintype "passive"))
      (node (ref "JP3") (pin "1") (pinfunction "1_1") (pintype "passive"))
    )
    (net (code "104") (name "RS-") (class "Default")
      (node (ref "J3") (pin "1") (pinfunction "1_1") (pintype "passive"))
      (node (ref "JP2") (pin "1") (pinfunction "1_1") (pintype "passive"))
    )
    (net (code "105") (name "S1") (class "Default")
      (node (ref "S1") (pin "1") (pinfunction "1_1") (pintype "passive"))
      (node (ref "U17") (pin "B9") (pinfunction "B9_B9") (pintype "bidirectional"))
    )
    (net (code "106") (name "S2") (class "Default")
      (node (ref "S2") (pin "1") (pinfunction "1_1") (pintype "passive"))
      (node (ref "U17") (pin "C13") (pinfunction "C13_C13") (pintype "bidirectional"))
    )
    (net (code "107") (name "SCL-TX") (class "Default")
      (node (ref "U17") (pin "B10") (pinfunction "B10_B10") (pintype "bidirectional"))
    )
    (net (code "108") (name "SDA-RX") (class "Default")
      (node (ref "U17") (pin "B11") (pinfunction "B11_B11") (pintype "bidirectional"))
    )
    (net (code "109") (name "VS") (class "Default")
      (node (ref "C13") (pin "1") (pinfunction "1_1") (pintype "passive"))
      (node (ref "C7") (pin "+") (pinfunction "+_+") (pintype "passive"))
      (node (ref "J5") (pin "D1") (pinfunction "D1_D1") (pintype "bidirectional"))
      (node (ref "J6") (pin "2") (pinfunction "2_2") (pintype "passive"))
      (node (ref "R85") (pin "2") (pinfunction "2_2") (pintype "passive"))
    )
    (net (code "110") (name "unconnected-(S1-Pad2)") (class "Default")
      (node (ref "S1") (pin "2") (pinfunction "2_2") (pintype "passive"))
    )
    (net (code "111") (name "unconnected-(S2-Pad2)") (class "Default")
      (node (ref "S2") (pin "2") (pinfunction "2_2") (pintype "passive"))
    )
    (net (code "112") (name "unconnected-(U17-PadA10)") (class "Default")
      (node (ref "U17") (pin "A10") (pinfunction "A10_A10") (pintype "bidirectional"))
    )
    (net (code "113") (name "unconnected-(U17-PadB3)") (class "Default")
      (node (ref "U17") (pin "B3") (pinfunction "B3_B3") (pintype "bidirectional"))
    )
    (net (code "114") (name "unconnected-(U17-PadB7)") (class "Default")
      (node (ref "U17") (pin "B7") (pinfunction "B7_B7") (pintype "bidirectional"))
    )
    (net (code "115") (name "unconnected-(U17-PadRST)") (class "Default")
      (node (ref "U17") (pin "RST") (pinfunction "RST_RST") (pintype "bidirectional"))
    )
    (net (code "116") (name "unconnected-(U17-VB-PadVBAT)") (class "Default")
      (node (ref "U17") (pin "VBAT") (pinfunction "VB_VBAT") (pintype "bidirectional"))
    )
  )
)
